# SoC.net
KiCad netlist of a schematic drawn in Altium Designer
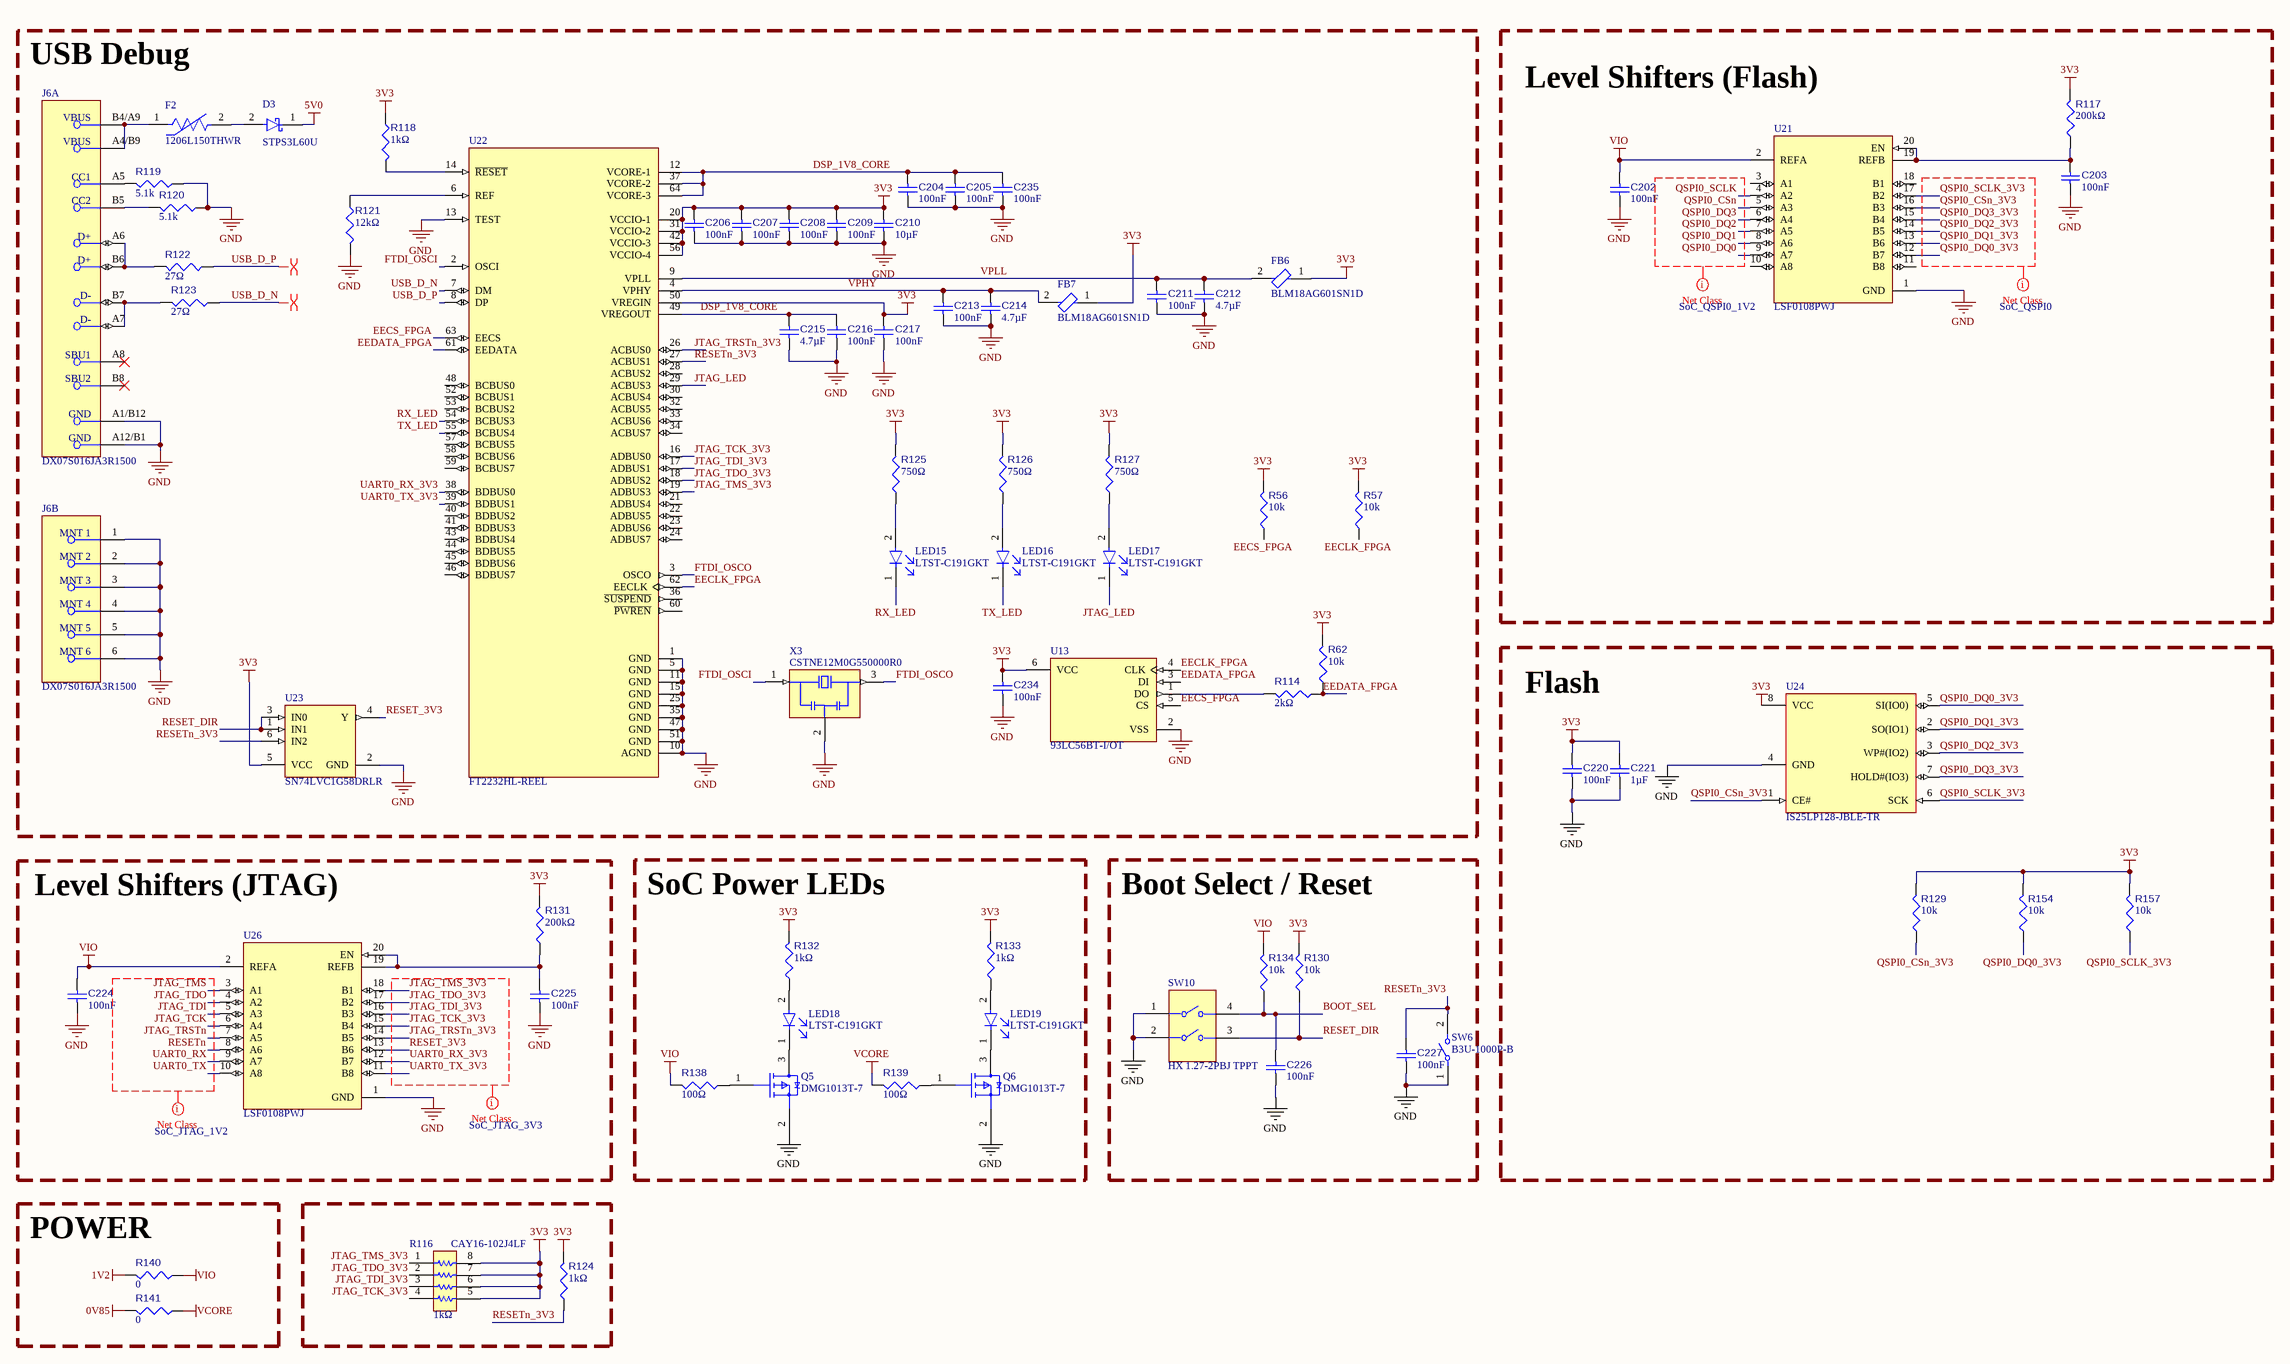
[diagram p0: SoC.SchDoc]

(export (version "E")
  (design (tool "Eeschema 10.0.6"))
  (components
    (comp (ref "C202")
      (value "100nF")
      (footprint "CAP-0402-MFG")
      (description "0402-100n-10%-16V-X7R-AECQ200")
      (fields (field (name "TOLERANCE") "10%") (field (name "MANUFACTURER PART NUMBER") "CL05B104KO5VPNC"))
      (libsource (lib "UC Berkeley – EE194") (part "CAP-NP-2P"))
    )
    (comp (ref "C203")
      (value "100nF")
      (footprint "CAP-0402-MFG")
      (description "0402-100n-10%-16V-X7R-AECQ200")
      (fields (field (name "TOLERANCE") "10%") (field (name "MANUFACTURER PART NUMBER") "CL05B104KO5VPNC"))
      (libsource (lib "UC Berkeley – EE194") (part "CAP-NP-2P"))
    )
    (comp (ref "C204")
      (value "100nF")
      (footprint "CAP-0402-MFG")
      (description "0402-100n-10%-16V-X7R-AECQ200")
      (fields (field (name "TOLERANCE") "10%") (field (name "MANUFACTURER PART NUMBER") "CL05B104KO5VPNC"))
      (libsource (lib "UC Berkeley – EE194") (part "CAP-NP-2P"))
    )
    (comp (ref "C205")
      (value "100nF")
      (footprint "CAP-0402-MFG")
      (description "0402-100n-10%-16V-X7R-AECQ200")
      (fields (field (name "TOLERANCE") "10%") (field (name "MANUFACTURER PART NUMBER") "CL05B104KO5VPNC"))
      (libsource (lib "UC Berkeley – EE194") (part "CAP-NP-2P"))
    )
    (comp (ref "C206")
      (value "100nF")
      (footprint "CAP-0402-MFG")
      (description "0402-100n-10%-16V-X7R-AECQ200")
      (fields (field (name "TOLERANCE") "10%") (field (name "MANUFACTURER PART NUMBER") "CL05B104KO5VPNC"))
      (libsource (lib "UC Berkeley – EE194") (part "CAP-NP-2P"))
    )
    (comp (ref "C207")
      (value "100nF")
      (footprint "CAP-0402-MFG")
      (description "0402-100n-10%-16V-X7R-AECQ200")
      (fields (field (name "TOLERANCE") "10%") (field (name "MANUFACTURER PART NUMBER") "CL05B104KO5VPNC"))
      (libsource (lib "UC Berkeley – EE194") (part "CAP-NP-2P"))
    )
    (comp (ref "C208")
      (value "100nF")
      (footprint "CAP-0402-MFG")
      (description "0402-100n-10%-16V-X7R-AECQ200")
      (fields (field (name "TOLERANCE") "10%") (field (name "MANUFACTURER PART NUMBER") "CL05B104KO5VPNC"))
      (libsource (lib "UC Berkeley – EE194") (part "CAP-NP-2P"))
    )
    (comp (ref "C209")
      (value "100nF")
      (footprint "CAP-0402-MFG")
      (description "0402-100n-10%-16V-X7R-AECQ200")
      (fields (field (name "TOLERANCE") "10%") (field (name "MANUFACTURER PART NUMBER") "CL05B104KO5VPNC"))
      (libsource (lib "UC Berkeley – EE194") (part "CAP-NP-2P"))
    )
    (comp (ref "C210")
      (value "10µF")
      (footprint "CAP-0603-MFG")
      (description "0603-10u-10%-16V-X5R-AECQ200")
      (fields (field (name "TOLERANCE") "10%") (field (name "MANUFACTURER PART NUMBER") "GRT188R61C106KE13J"))
      (libsource (lib "UC Berkeley – EE194") (part "CAP-NP-2P"))
    )
    (comp (ref "C211")
      (value "100nF")
      (footprint "CAP-0402-MFG")
      (description "0402-100n-10%-16V-X7R-AECQ200")
      (fields (field (name "TOLERANCE") "10%") (field (name "MANUFACTURER PART NUMBER") "CL05B104KO5VPNC"))
      (libsource (lib "UC Berkeley – EE194") (part "CAP-NP-2P"))
    )
    (comp (ref "C212")
      (value "4.7µF")
      (footprint "CAP-0402-MFG")
      (description "0402-4.7u-20%-25V-X5R")
      (fields (field (name "TOLERANCE") "20%") (field (name "MANUFACTURER PART NUMBER") "GRM155R61E475ME15D"))
      (libsource (lib "UC Berkeley – EE194") (part "CAP-NP-2P"))
    )
    (comp (ref "C213")
      (value "100nF")
      (footprint "CAP-0402-MFG")
      (description "0402-100n-10%-16V-X7R-AECQ200")
      (fields (field (name "TOLERANCE") "10%") (field (name "MANUFACTURER PART NUMBER") "CL05B104KO5VPNC"))
      (libsource (lib "UC Berkeley – EE194") (part "CAP-NP-2P"))
    )
    (comp (ref "C214")
      (value "4.7µF")
      (footprint "CAP-0402-MFG")
      (description "0402-4.7u-20%-25V-X5R")
      (fields (field (name "TOLERANCE") "20%") (field (name "MANUFACTURER PART NUMBER") "GRM155R61E475ME15D"))
      (libsource (lib "UC Berkeley – EE194") (part "CAP-NP-2P"))
    )
    (comp (ref "C215")
      (value "4.7µF")
      (footprint "CAP-0402-MFG")
      (description "0402-4.7u-20%-25V-X5R")
      (fields (field (name "TOLERANCE") "20%") (field (name "MANUFACTURER PART NUMBER") "GRM155R61E475ME15D"))
      (libsource (lib "UC Berkeley – EE194") (part "CAP-NP-2P"))
    )
    (comp (ref "C216")
      (value "100nF")
      (footprint "CAP-0402-MFG")
      (description "0402-100n-10%-16V-X7R-AECQ200")
      (fields (field (name "TOLERANCE") "10%") (field (name "MANUFACTURER PART NUMBER") "CL05B104KO5VPNC"))
      (libsource (lib "UC Berkeley – EE194") (part "CAP-NP-2P"))
    )
    (comp (ref "C217")
      (value "100nF")
      (footprint "CAP-0402-MFG")
      (description "0402-100n-10%-16V-X7R-AECQ200")
      (fields (field (name "TOLERANCE") "10%") (field (name "MANUFACTURER PART NUMBER") "CL05B104KO5VPNC"))
      (libsource (lib "UC Berkeley – EE194") (part "CAP-NP-2P"))
    )
    (comp (ref "C220")
      (value "100nF")
      (footprint "CAP-0402-MFG")
      (description "0402-100n-10%-16V-X7R-AECQ200")
      (fields (field (name "TOLERANCE") "10%") (field (name "MANUFACTURER PART NUMBER") "CL05B104KO5VPNC"))
      (libsource (lib "UC Berkeley – EE194") (part "CAP-NP-2P"))
    )
    (comp (ref "C221")
      (value "1µF")
      (footprint "CAP-0402-MFG")
      (description "0402-1u-10%-16V-X6S-AECQ200")
      (fields (field (name "MANUFACTURER PART NUMBER") "GRT155C81C105KE13J") (field (name "TOLERANCE") "10%"))
      (libsource (lib "UC Berkeley – EE194") (part "CAP-NP-2P"))
    )
    (comp (ref "C224")
      (value "100nF")
      (footprint "CAP-0402-MFG")
      (description "0402-100n-10%-16V-X7R-AECQ200")
      (fields (field (name "TOLERANCE") "10%") (field (name "MANUFACTURER PART NUMBER") "CL05B104KO5VPNC"))
      (libsource (lib "UC Berkeley – EE194") (part "CAP-NP-2P"))
    )
    (comp (ref "C225")
      (value "100nF")
      (footprint "CAP-0402-MFG")
      (description "0402-100n-10%-16V-X7R-AECQ200")
      (fields (field (name "TOLERANCE") "10%") (field (name "MANUFACTURER PART NUMBER") "CL05B104KO5VPNC"))
      (libsource (lib "UC Berkeley – EE194") (part "CAP-NP-2P"))
    )
    (comp (ref "C226")
      (value "100nF")
      (footprint "CAP-0402-MFG")
      (description "0402-100n-10%-16V-X7R-AECQ200")
      (fields (field (name "TOLERANCE") "10%") (field (name "MANUFACTURER PART NUMBER") "CL05B104KO5VPNC"))
      (libsource (lib "UC Berkeley – EE194") (part "CAP-NP-2P"))
    )
    (comp (ref "C227")
      (value "100nF")
      (footprint "CAP-0402-MFG")
      (description "0402-100n-10%-16V-X7R-AECQ200")
      (fields (field (name "TOLERANCE") "10%") (field (name "MANUFACTURER PART NUMBER") "CL05B104KO5VPNC"))
      (libsource (lib "UC Berkeley – EE194") (part "CAP-NP-2P"))
    )
    (comp (ref "C234")
      (value "100nF")
      (footprint "CAP-0402-MFG")
      (description "0402-100n-10%-16V-X7R-AECQ200")
      (fields (field (name "TOLERANCE") "10%") (field (name "MANUFACTURER PART NUMBER") "CL05B104KO5VPNC"))
      (libsource (lib "UC Berkeley – EE194") (part "CAP-NP-2P"))
    )
    (comp (ref "C235")
      (value "100nF")
      (footprint "CAP-0402-MFG")
      (description "0402-100n-10%-16V-X7R-AECQ200")
      (fields (field (name "TOLERANCE") "10%") (field (name "MANUFACTURER PART NUMBER") "CL05B104KO5VPNC"))
      (libsource (lib "UC Berkeley – EE194") (part "CAP-NP-2P"))
    )
    (comp (ref "D3")
      (value "STPS3L60U")
      (footprint "FP-DO214AA-MFG")
      (description "DO214AA-UNI-SCHOTTKY-60V-3A-590mV")
      (libsource (lib "UC Berkeley – EE194") (part "SCHOTTKY-UNI-2P-DIODE"))
    )
    (comp (ref "F2")
      (value "1206L150THWR")
      (footprint "FP-1206L050YR-MFG")
      (description "PTC Resettable Fuse 1.5A(hold) 3A(trip) 8VDC 100A 0.8W 0.3s 0.04Ohm SMD Solder Pad 1206 T/R")
      (libsource (lib "UC Berkeley – EE194") (part "FUSE-2P"))
    )
    (comp (ref "FB6")
      (value "BLM18AG601SN1D")
      (footprint "FERRITEBEAD-0603-MFG")
      (description "Ferrite Beads Multi-Layer 600Ohm 25% 100MHz 500mA 380mOhm DCR 0603 Automotive Paper T/R")
      (fields (field (name "TOLERANCE") "25%"))
      (libsource (lib "UC Berkeley – EE194") (part "FERRITE-BEAD-2P"))
    )
    (comp (ref "FB7")
      (value "BLM18AG601SN1D")
      (footprint "FERRITEBEAD-0603-MFG")
      (description "Ferrite Beads Multi-Layer 600Ohm 25% 100MHz 500mA 380mOhm DCR 0603 Automotive Paper T/R")
      (fields (field (name "TOLERANCE") "25%"))
      (libsource (lib "UC Berkeley – EE194") (part "FERRITE-BEAD-2P"))
    )
    (comp (ref "J6")
      (value "DX07S016JA3R1500")
      (footprint "FP-DX07S016JA3R1500-MFG")
      (description "Receptacle, 16 Position, 1-Row SMT, without Rear Shield, Shell-DIP Length 1.2mm")
      (libsource (lib "UC Berkeley – EE194") (part "DX07S016JA3R1500"))
    )
    (comp (ref "LED15")
      (value "LTST-C191GKT")
      (footprint "LED-0603-MFG")
      (description "LED yellow green 0603 wavelength 569nm light intensity 12mcd Front Mounting")
      (libsource (lib "UC Berkeley – EE194") (part "LED"))
    )
    (comp (ref "LED16")
      (value "LTST-C191GKT")
      (footprint "LED-0603-MFG")
      (description "LED yellow green 0603 wavelength 569nm light intensity 12mcd Front Mounting")
      (libsource (lib "UC Berkeley – EE194") (part "LED"))
    )
    (comp (ref "LED17")
      (value "LTST-C191GKT")
      (footprint "LED-0603-MFG")
      (description "LED yellow green 0603 wavelength 569nm light intensity 12mcd Front Mounting")
      (libsource (lib "UC Berkeley – EE194") (part "LED"))
    )
    (comp (ref "LED18")
      (value "LTST-C191GKT")
      (footprint "LED-0603-MFG")
      (description "LED yellow green 0603 wavelength 569nm light intensity 12mcd Front Mounting")
      (libsource (lib "UC Berkeley – EE194") (part "LED"))
    )
    (comp (ref "LED19")
      (value "LTST-C191GKT")
      (footprint "LED-0603-MFG")
      (description "LED yellow green 0603 wavelength 569nm light intensity 12mcd Front Mounting")
      (libsource (lib "UC Berkeley – EE194") (part "LED"))
    )
    (comp (ref "Q5")
      (value "DMG1013T-7")
      (footprint "FP-SOT523-MFG")
      (description "P-Channel 20 V 0.7 Ohm 0.27 W Enhancement Mode Mosfet - SOT-523")
      (libsource (lib "UC Berkeley – EE194") (part "P-MOSFET-3P"))
    )
    (comp (ref "Q6")
      (value "DMG1013T-7")
      (footprint "FP-SOT523-MFG")
      (description "P-Channel 20 V 0.7 Ohm 0.27 W Enhancement Mode Mosfet - SOT-523")
      (libsource (lib "UC Berkeley – EE194") (part "P-MOSFET-3P"))
    )
    (comp (ref "R56")
      (value "10k")
      (footprint "RES-0402")
      (description "0402-10k-1%-1/16W-AEC-Q200")
      (fields (field (name "TOLERANCE") "1%") (field (name "MANUFACTURER PART NUMBER") "AC0402FR-0710KL"))
      (libsource (lib "UC Berkeley – EE194") (part "RES-2P"))
    )
    (comp (ref "R57")
      (value "10k")
      (footprint "RES-0402")
      (description "0402-10k-1%-1/16W-AEC-Q200")
      (fields (field (name "TOLERANCE") "1%") (field (name "MANUFACTURER PART NUMBER") "AC0402FR-0710KL"))
      (libsource (lib "UC Berkeley – EE194") (part "RES-2P"))
    )
    (comp (ref "R62")
      (value "10k")
      (footprint "RES-0402")
      (description "0402-10k-1%-1/16W-AEC-Q200")
      (fields (field (name "TOLERANCE") "1%") (field (name "MANUFACTURER PART NUMBER") "AC0402FR-0710KL"))
      (libsource (lib "UC Berkeley – EE194") (part "RES-2P"))
    )
    (comp (ref "R114")
      (value "2kΩ")
      (footprint "RES-0402")
      (description "0402-2k-1%-1/16W-AEC-Q200")
      (fields (field (name "TOLERANCE") "1%") (field (name "POWER") "63mW"))
      (libsource (lib "UC Berkeley – EE194") (part "RES-2P"))
    )
    (comp (ref "R116")
      (value "CAY16-102J4LF")
      (footprint "RES-4x0603-MFG")
      (description "Res Thick Film Array 1K Ohm 5% 0.25W(1/4W) ±200ppm/C ISOL 8-Pin 1206(4 X 0603) Convex SMD T/R")
      (fields (field (name "TOLERANCE") "5%") (field (name "ALTIUM_VALUE") "1kΩ"))
      (libsource (lib "UC Berkeley – EE194") (part "RES-x4-8P"))
    )
    (comp (ref "R117")
      (value "200kΩ")
      (footprint "RES-0402")
      (description "0402-200k-1%-1/16W-AEC-Q200")
      (fields (field (name "TOLERANCE") "1%") (field (name "POWER") "63mW"))
      (libsource (lib "UC Berkeley – EE194") (part "RES-2P"))
    )
    (comp (ref "R118")
      (value "1kΩ")
      (footprint "RES-0402")
      (description "0402-1k-1%-1/16W-AEC-Q200")
      (fields (field (name "MANUFACTURER PART NUMBER") "AC0402FR-071KL") (field (name "POWER") "63mW"))
      (libsource (lib "UC Berkeley – EE194") (part "RES-2P"))
    )
    (comp (ref "R119")
      (value "5.1k")
      (footprint "RES-0402")
      (description "0402-5.1k-1%-1/16W-AEC-Q200")
      (fields (field (name "TOLERANCE") "1%") (field (name "MANUFACTURER PART NUMBER") "AC0402FR-075K1L"))
      (libsource (lib "UC Berkeley – EE194") (part "RES-2P"))
    )
    (comp (ref "R120")
      (value "5.1k")
      (footprint "RES-0402")
      (description "0402-5.1k-1%-1/16W-AEC-Q200")
      (fields (field (name "TOLERANCE") "1%") (field (name "MANUFACTURER PART NUMBER") "AC0402FR-075K1L"))
      (libsource (lib "UC Berkeley – EE194") (part "RES-2P"))
    )
    (comp (ref "R121")
      (value "12kΩ")
      (footprint "RES-0402")
      (description "0402-12k-1%-1/16W-AEC-Q200")
      (fields (field (name "POWER") "63mW") (field (name "TOLERANCE") "1%"))
      (libsource (lib "UC Berkeley – EE194") (part "RES-2P"))
    )
    (comp (ref "R122")
      (value "27Ω")
      (footprint "RES-0402")
      (description "0402-27-1%-1/16W-AEC-Q200")
      (fields (field (name "TOLERANCE") "1%") (field (name "MANUFACTURER PART NUMBER") "AC0402FR-0727RL"))
      (libsource (lib "UC Berkeley – EE194") (part "RES-2P"))
    )
    (comp (ref "R123")
      (value "27Ω")
      (footprint "RES-0402")
      (description "0402-27-1%-1/16W-AEC-Q200")
      (fields (field (name "TOLERANCE") "1%") (field (name "MANUFACTURER PART NUMBER") "AC0402FR-0727RL"))
      (libsource (lib "UC Berkeley – EE194") (part "RES-2P"))
    )
    (comp (ref "R124")
      (value "1kΩ")
      (footprint "RES-0402")
      (description "0402-1k-1%-1/16W-AEC-Q200")
      (fields (field (name "MANUFACTURER PART NUMBER") "AC0402FR-071KL") (field (name "POWER") "63mW"))
      (libsource (lib "UC Berkeley – EE194") (part "RES-2P"))
    )
    (comp (ref "R125")
      (value "750Ω")
      (footprint "RES-0402")
      (description "0402-750-1%-1/16W-AEC-Q200")
      (fields (field (name "TOLERANCE") "1%") (field (name "POWER") "63mW"))
      (libsource (lib "UC Berkeley – EE194") (part "RES-2P"))
    )
    (comp (ref "R126")
      (value "750Ω")
      (footprint "RES-0402")
      (description "0402-750-1%-1/16W-AEC-Q200")
      (fields (field (name "TOLERANCE") "1%") (field (name "POWER") "63mW"))
      (libsource (lib "UC Berkeley – EE194") (part "RES-2P"))
    )
    (comp (ref "R127")
      (value "750Ω")
      (footprint "RES-0402")
      (description "0402-750-1%-1/16W-AEC-Q200")
      (fields (field (name "TOLERANCE") "1%") (field (name "POWER") "63mW"))
      (libsource (lib "UC Berkeley – EE194") (part "RES-2P"))
    )
    (comp (ref "R129")
      (value "10k")
      (footprint "RES-0402")
      (description "0402-10k-1%-1/16W-AEC-Q200")
      (fields (field (name "TOLERANCE") "1%") (field (name "MANUFACTURER PART NUMBER") "AC0402FR-0710KL"))
      (libsource (lib "UC Berkeley – EE194") (part "RES-2P"))
    )
    (comp (ref "R130")
      (value "10k")
      (footprint "RES-0402")
      (description "0402-10k-1%-1/16W-AEC-Q200")
      (fields (field (name "TOLERANCE") "1%") (field (name "MANUFACTURER PART NUMBER") "AC0402FR-0710KL"))
      (libsource (lib "UC Berkeley – EE194") (part "RES-2P"))
    )
    (comp (ref "R131")
      (value "200kΩ")
      (footprint "RES-0402")
      (description "0402-200k-1%-1/16W-AEC-Q200")
      (fields (field (name "TOLERANCE") "1%") (field (name "POWER") "63mW"))
      (libsource (lib "UC Berkeley – EE194") (part "RES-2P"))
    )
    (comp (ref "R132")
      (value "1kΩ")
      (footprint "RES-0402")
      (description "0402-1k-1%-1/16W-AEC-Q200")
      (fields (field (name "MANUFACTURER PART NUMBER") "AC0402FR-071KL") (field (name "POWER") "63mW"))
      (libsource (lib "UC Berkeley – EE194") (part "RES-2P"))
    )
    (comp (ref "R133")
      (value "1kΩ")
      (footprint "RES-0402")
      (description "0402-1k-1%-1/16W-AEC-Q200")
      (fields (field (name "MANUFACTURER PART NUMBER") "AC0402FR-071KL") (field (name "POWER") "63mW"))
      (libsource (lib "UC Berkeley – EE194") (part "RES-2P"))
    )
    (comp (ref "R134")
      (value "10k")
      (footprint "RES-0402")
      (description "0402-10k-1%-1/16W-AEC-Q200")
      (fields (field (name "TOLERANCE") "1%") (field (name "MANUFACTURER PART NUMBER") "AC0402FR-0710KL"))
      (libsource (lib "UC Berkeley – EE194") (part "RES-2P"))
    )
    (comp (ref "R138")
      (value "100Ω")
      (footprint "RES-0402")
      (description "0402-100-1%-1/16W-AEC-Q200")
      (fields (field (name "MANUFACTURER PART NUMBER") "AC0402FR-07100RL") (field (name "POWER") "63mW"))
      (libsource (lib "UC Berkeley – EE194") (part "RES-2P"))
    )
    (comp (ref "R139")
      (value "100Ω")
      (footprint "RES-0402")
      (description "0402-100-1%-1/16W-AEC-Q200")
      (fields (field (name "MANUFACTURER PART NUMBER") "AC0402FR-07100RL") (field (name "POWER") "63mW"))
      (libsource (lib "UC Berkeley – EE194") (part "RES-2P"))
    )
    (comp (ref "R140")
      (value "0")
      (footprint "RES-0603-MFG")
      (description "0603-0-1A-AECQ200")
      (fields (field (name "MANUFACTURER PART NUMBER") "AC0603FR-070RL") (field (name "TOLERANCE") "1%"))
      (libsource (lib "UC Berkeley – EE194") (part "RES-2P"))
    )
    (comp (ref "R141")
      (value "0")
      (footprint "RES-0603-MFG")
      (description "0603-0-1A-AECQ200")
      (fields (field (name "MANUFACTURER PART NUMBER") "AC0603FR-070RL") (field (name "TOLERANCE") "1%"))
      (libsource (lib "UC Berkeley – EE194") (part "RES-2P"))
    )
    (comp (ref "R154")
      (value "10k")
      (footprint "RES-0402")
      (description "0402-10k-1%-1/16W-AEC-Q200")
      (fields (field (name "TOLERANCE") "1%") (field (name "MANUFACTURER PART NUMBER") "AC0402FR-0710KL"))
      (libsource (lib "UC Berkeley – EE194") (part "RES-2P"))
    )
    (comp (ref "R157")
      (value "10k")
      (footprint "RES-0402")
      (description "0402-10k-1%-1/16W-AEC-Q200")
      (fields (field (name "TOLERANCE") "1%") (field (name "MANUFACTURER PART NUMBER") "AC0402FR-0710KL"))
      (libsource (lib "UC Berkeley – EE194") (part "RES-2P"))
    )
    (comp (ref "SW6")
      (value "B3U-1000P-B")
      (footprint "FP-B3U-1000P-B-MFG")
      (description "Switch Tactile N.O. SPST Round Button Gull Wing 0.05A 12VDC 1.5N SMD Embossed T/R")
      (libsource (lib "UC Berkeley – EE194") (part "SWITCH-SPST-OFF-MOM-2P"))
    )
    (comp (ref "SW10")
      (value "HX 1.27-2PBJ TPPT")
      (footprint "HX 1.27-2PBJ TPPT-Footprint-1")
      (description "Dual 1.27mm SMT DIP Switch")
      (libsource (lib "UC Berkeley – EE194") (part "HX 1.27-2PBJ TPPT-Symbol-1"))
    )
    (comp (ref "U13")
      (value "93LC56BT-I/OT")
      (footprint "FP-SOT-23-6-MFG")
      (description "Microwire Serial EEPROM Family, 2.5Vto 5.5V' 2 MHz, -40°Cto 125°C, SOT-23-6, RoHS")
      (libsource (lib "UC Berkeley – EE194") (part "93LC56BT-I/OT"))
    )
    (comp (ref "U21")
      (value "LSF0108PWJ")
      (footprint "FP-TSSOP20-MFG")
      (description "LSF0108 - 8-bit bidirectional multi-voltage level translator; open-drain; push-pull")
      (libsource (lib "UC Berkeley – EE194") (part "LSF0108PWJ"))
    )
    (comp (ref "U22")
      (value "FT2232HL-REEL")
      (footprint "LQFP-64-MFG")
      (description "USB Hi-Speed to Dual Channel Serial UART/FIFO/JTAG/SPI/I2C IC - LQFP-64")
      (libsource (lib "UC Berkeley – EE194") (part "FT2232HL-REEL"))
    )
    (comp (ref "U23")
      (value "SN74LVC1G58DRLR")
      (footprint "DRL0006A_M")
      (description "Configurable Multiple-Function Gate 6-SOT-5X3 -40 to 125")
      (libsource (lib "UC Berkeley – EE194") (part "TI-SN74XXX1GXX-6"))
    )
    (comp (ref "U24")
      (value "IS25LP128-JBLE-TR")
      (footprint "FP-SOIC8-MFG")
      (description "NOR Flash Serial (SPI, Dual SPI, Quad SPI) 2.5V/3V/3.3V 128M-bit 16M x 8 8ns 8-Pin SOIC T/R")
      (fields (field (name "COPYRIGHT") "Copyright (C) 2025 Ultra Librarian. All rights reserved."))
      (libsource (lib "UC Berkeley – EE194") (part "IS25LP128-JBLE-TR"))
    )
    (comp (ref "U26")
      (value "LSF0108PWJ")
      (footprint "FP-TSSOP20-MFG")
      (description "LSF0108 - 8-bit bidirectional multi-voltage level translator; open-drain; push-pull")
      (libsource (lib "UC Berkeley – EE194") (part "LSF0108PWJ"))
    )
    (comp (ref "X3")
      (value "CSTNE12M0G550000R0")
      (footprint "OSC-SMD3213-3P")
      (description "Ceramic Resonator 12MHz ±0.5% (Tol) ±0.2% (Stability) 33pF 30Ohm 3-Pin CSMD T/R")
      (libsource (lib "UC Berkeley – EE194") (part "CSTNE12M0G550000R0"))
    )
  )
  (nets
    (net (code "2") (name "/BOOT_SEL") (class "Default")
      (node (ref "C226") (pin "1") (pinfunction "1_1") (pintype "passive"))
      (node (ref "R134") (pin "1") (pinfunction "1_1") (pintype "passive"))
      (node (ref "SW10") (pin "4") (pinfunction "4_4") (pintype "passive"))
    )
    (net (code "3") (name "/DSP_1V8_CORE") (class "Default")
      (node (ref "C204") (pin "1") (pinfunction "1_1") (pintype "passive"))
      (node (ref "C205") (pin "1") (pinfunction "1_1") (pintype "passive"))
      (node (ref "C215") (pin "1") (pinfunction "1_1") (pintype "passive"))
      (node (ref "C216") (pin "1") (pinfunction "1_1") (pintype "passive"))
      (node (ref "C235") (pin "1") (pinfunction "1_1") (pintype "passive"))
      (node (ref "U22") (pin "12") (pinfunction "VCORE-1_12") (pintype "power_in"))
      (node (ref "U22") (pin "37") (pinfunction "VCORE-2_37") (pintype "power_in"))
      (node (ref "U22") (pin "49") (pinfunction "VREGOUT_49") (pintype "power_in"))
      (node (ref "U22") (pin "64") (pinfunction "VCORE-3_64") (pintype "power_in"))
    )
    (net (code "4") (name "/EECLK_FPGA") (class "Default")
      (node (ref "R57") (pin "1") (pinfunction "1_1") (pintype "passive"))
      (node (ref "U13") (pin "4") (pinfunction "CLK_4") (pintype "input"))
      (node (ref "U22") (pin "62") (pinfunction "EECLK_62") (pintype "output"))
    )
    (net (code "5") (name "/EECS_FPGA") (class "Default")
      (node (ref "R56") (pin "1") (pinfunction "1_1") (pintype "passive"))
      (node (ref "U13") (pin "5") (pinfunction "CS_5") (pintype "input"))
      (node (ref "U22") (pin "63") (pinfunction "EECS_63") (pintype "bidirectional"))
    )
    (net (code "6") (name "/EEDATA_FPGA") (class "Default")
      (node (ref "R114") (pin "1") (pinfunction "1_1") (pintype "passive"))
      (node (ref "R62") (pin "1") (pinfunction "1_1") (pintype "passive"))
      (node (ref "U13") (pin "3") (pinfunction "DI_3") (pintype "input"))
      (node (ref "U22") (pin "61") (pinfunction "EEDATA_61") (pintype "bidirectional"))
    )
    (net (code "7") (name "/FTDI_OSCI") (class "Default")
      (node (ref "U22") (pin "2") (pinfunction "OSCI_2") (pintype "input"))
      (node (ref "X3") (pin "1") (pinfunction "IN_1") (pintype "input"))
    )
    (net (code "8") (name "/FTDI_OSCO") (class "Default")
      (node (ref "U22") (pin "3") (pinfunction "OSCO_3") (pintype "output"))
      (node (ref "X3") (pin "3") (pinfunction "OUT_3") (pintype "output"))
    )
    (net (code "9") (name "/JTAG_LED") (class "Default")
      (node (ref "LED17") (pin "1") (pinfunction "C_1") (pintype "passive"))
      (node (ref "U22") (pin "29") (pinfunction "ACBUS3_29") (pintype "bidirectional"))
    )
    (net (code "10") (name "/JTAG_TCK") (class "Default")
      (node (ref "U26") (pin "6") (pinfunction "A4_6") (pintype "bidirectional"))
    )
    (net (code "11") (name "/JTAG_TCK_3V3") (class "Default")
      (node (ref "R116") (pin "4") (pinfunction "4_4") (pintype "passive"))
      (node (ref "U22") (pin "16") (pinfunction "ADBUS0_16") (pintype "bidirectional"))
      (node (ref "U26") (pin "15") (pinfunction "B4_15") (pintype "bidirectional"))
    )
    (net (code "12") (name "/JTAG_TDI") (class "Default")
      (node (ref "U26") (pin "5") (pinfunction "A3_5") (pintype "bidirectional"))
    )
    (net (code "13") (name "/JTAG_TDI_3V3") (class "Default")
      (node (ref "R116") (pin "3") (pinfunction "3_3") (pintype "passive"))
      (node (ref "U22") (pin "17") (pinfunction "ADBUS1_17") (pintype "bidirectional"))
      (node (ref "U26") (pin "16") (pinfunction "B3_16") (pintype "bidirectional"))
    )
    (net (code "14") (name "/JTAG_TDO") (class "Default")
      (node (ref "U26") (pin "4") (pinfunction "A2_4") (pintype "bidirectional"))
    )
    (net (code "15") (name "/JTAG_TDO_3V3") (class "Default")
      (node (ref "R116") (pin "2") (pinfunction "2_2") (pintype "passive"))
      (node (ref "U22") (pin "18") (pinfunction "ADBUS2_18") (pintype "bidirectional"))
      (node (ref "U26") (pin "17") (pinfunction "B2_17") (pintype "bidirectional"))
    )
    (net (code "16") (name "/JTAG_TMS") (class "Default")
      (node (ref "U26") (pin "3") (pinfunction "A1_3") (pintype "bidirectional"))
    )
    (net (code "17") (name "/JTAG_TMS_3V3") (class "Default")
      (node (ref "R116") (pin "1") (pinfunction "1_1") (pintype "passive"))
      (node (ref "U22") (pin "19") (pinfunction "ADBUS3_19") (pintype "bidirectional"))
      (node (ref "U26") (pin "18") (pinfunction "B1_18") (pintype "bidirectional"))
    )
    (net (code "18") (name "/JTAG_TRSTn") (class "Default")
      (node (ref "U26") (pin "7") (pinfunction "A5_7") (pintype "bidirectional"))
    )
    (net (code "19") (name "/JTAG_TRSTn_3V3") (class "Default")
      (node (ref "U22") (pin "26") (pinfunction "ACBUS0_26") (pintype "bidirectional"))
      (node (ref "U26") (pin "14") (pinfunction "B5_14") (pintype "bidirectional"))
    )
    (net (code "20") (name "/QSPI0_CSn") (class "Default")
      (node (ref "U21") (pin "5") (pinfunction "A3_5") (pintype "bidirectional"))
    )
    (net (code "21") (name "/QSPI0_CSn_3V3") (class "Default")
      (node (ref "R129") (pin "1") (pinfunction "1_1") (pintype "passive"))
      (node (ref "U21") (pin "16") (pinfunction "B3_16") (pintype "bidirectional"))
      (node (ref "U24") (pin "1") (pinfunction "CE#_1") (pintype "input"))
    )
    (net (code "22") (name "/QSPI0_DQ0") (class "Default")
      (node (ref "U21") (pin "9") (pinfunction "A7_9") (pintype "bidirectional"))
    )
    (net (code "23") (name "/QSPI0_DQ0_3V3") (class "Default")
      (node (ref "R154") (pin "1") (pinfunction "1_1") (pintype "passive"))
      (node (ref "U21") (pin "12") (pinfunction "B7_12") (pintype "bidirectional"))
      (node (ref "U24") (pin "5") (pinfunction "SI(IO0)_5") (pintype "bidirectional"))
    )
    (net (code "24") (name "/QSPI0_DQ1") (class "Default")
      (node (ref "U21") (pin "8") (pinfunction "A6_8") (pintype "bidirectional"))
    )
    (net (code "25") (name "/QSPI0_DQ1_3V3") (class "Default")
      (node (ref "U21") (pin "13") (pinfunction "B6_13") (pintype "bidirectional"))
      (node (ref "U24") (pin "2") (pinfunction "SO(IO1)_2") (pintype "bidirectional"))
    )
    (net (code "26") (name "/QSPI0_DQ2") (class "Default")
      (node (ref "U21") (pin "7") (pinfunction "A5_7") (pintype "bidirectional"))
    )
    (net (code "27") (name "/QSPI0_DQ2_3V3") (class "Default")
      (node (ref "U21") (pin "14") (pinfunction "B5_14") (pintype "bidirectional"))
      (node (ref "U24") (pin "3") (pinfunction "WP#(IO2)_3") (pintype "bidirectional"))
    )
    (net (code "28") (name "/QSPI0_DQ3") (class "Default")
      (node (ref "U21") (pin "6") (pinfunction "A4_6") (pintype "bidirectional"))
    )
    (net (code "29") (name "/QSPI0_DQ3_3V3") (class "Default")
      (node (ref "U21") (pin "15") (pinfunction "B4_15") (pintype "bidirectional"))
      (node (ref "U24") (pin "7") (pinfunction "HOLD#(IO3)_7") (pintype "bidirectional"))
    )
    (net (code "30") (name "/QSPI0_SCLK") (class "Default")
      (node (ref "U21") (pin "4") (pinfunction "A2_4") (pintype "bidirectional"))
    )
    (net (code "31") (name "/QSPI0_SCLK_3V3") (class "Default")
      (node (ref "R157") (pin "1") (pinfunction "1_1") (pintype "passive"))
      (node (ref "U21") (pin "17") (pinfunction "B2_17") (pintype "bidirectional"))
      (node (ref "U24") (pin "6") (pinfunction "SCK_6") (pintype "input"))
    )
    (net (code "32") (name "/RESET_3V3") (class "Default")
      (node (ref "U23") (pin "4") (pinfunction "Y_4") (pintype "output"))
      (node (ref "U26") (pin "13") (pinfunction "B6_13") (pintype "bidirectional"))
    )
    (net (code "33") (name "/RESET_DIR") (class "Default")
      (node (ref "R130") (pin "1") (pinfunction "1_1") (pintype "passive"))
      (node (ref "SW10") (pin "3") (pinfunction "3_3") (pintype "passive"))
      (node (ref "U23") (pin "1") (pinfunction "IN1_1") (pintype "input"))
      (node (ref "U23") (pin "3") (pinfunction "IN0_3") (pintype "input"))
    )
    (net (code "34") (name "/RESETn") (class "Default")
      (node (ref "U26") (pin "8") (pinfunction "A6_8") (pintype "bidirectional"))
    )
    (net (code "35") (name "/RESETn_3V3") (class "Default")
      (node (ref "C227") (pin "1") (pinfunction "1_1") (pintype "passive"))
      (node (ref "R124") (pin "1") (pinfunction "1_1") (pintype "passive"))
      (node (ref "SW6") (pin "2") (pinfunction "2_2") (pintype "passive"))
      (node (ref "U22") (pin "27") (pinfunction "ACBUS1_27") (pintype "bidirectional"))
      (node (ref "U23") (pin "6") (pinfunction "IN2_6") (pintype "input"))
    )
    (net (code "36") (name "/RX_LED") (class "Default")
      (node (ref "LED15") (pin "1") (pinfunction "C_1") (pintype "passive"))
      (node (ref "U22") (pin "54") (pinfunction "BCBUS3_54") (pintype "bidirectional"))
    )
    (net (code "37") (name "/TX_LED") (class "Default")
      (node (ref "LED16") (pin "1") (pinfunction "C_1") (pintype "passive"))
      (node (ref "U22") (pin "55") (pinfunction "BCBUS4_55") (pintype "bidirectional"))
    )
    (net (code "38") (name "/UART0_RX") (class "Default")
      (node (ref "U26") (pin "9") (pinfunction "A7_9") (pintype "bidirectional"))
    )
    (net (code "39") (name "/UART0_RX_3V3") (class "Default")
      (node (ref "U22") (pin "38") (pinfunction "BDBUS0_38") (pintype "bidirectional"))
      (node (ref "U26") (pin "12") (pinfunction "B7_12") (pintype "bidirectional"))
    )
    (net (code "40") (name "/UART0_TX") (class "Default")
      (node (ref "U26") (pin "10") (pinfunction "A8_10") (pintype "bidirectional"))
    )
    (net (code "41") (name "/UART0_TX_3V3") (class "Default")
      (node (ref "U22") (pin "39") (pinfunction "BDBUS1_39") (pintype "bidirectional"))
      (node (ref "U26") (pin "11") (pinfunction "B8_11") (pintype "bidirectional"))
    )
    (net (code "42") (name "/USB_D_N") (class "Default")
      (node (ref "R123") (pin "1") (pinfunction "1_1") (pintype "passive"))
      (node (ref "U22") (pin "7") (pinfunction "DM_7") (pintype "bidirectional"))
    )
    (net (code "43") (name "/USB_D_P") (class "Default")
      (node (ref "R122") (pin "1") (pinfunction "1_1") (pintype "passive"))
      (node (ref "U22") (pin "8") (pinfunction "DP_8") (pintype "bidirectional"))
    )
    (net (code "44") (name "/VPHY") (class "Default")
      (node (ref "C213") (pin "1") (pinfunction "1_1") (pintype "passive"))
      (node (ref "C214") (pin "1") (pinfunction "1_1") (pintype "passive"))
      (node (ref "FB7") (pin "2") (pinfunction "2_2") (pintype "passive"))
      (node (ref "U22") (pin "4") (pinfunction "VPHY_4") (pintype "power_in"))
    )
    (net (code "45") (name "/VPLL") (class "Default")
      (node (ref "C211") (pin "1") (pinfunction "1_1") (pintype "passive"))
      (node (ref "C212") (pin "1") (pinfunction "1_1") (pintype "passive"))
      (node (ref "FB6") (pin "2") (pinfunction "2_2") (pintype "passive"))
      (node (ref "U22") (pin "9") (pinfunction "VPLL_9") (pintype "power_in"))
    )
    (net (code "46") (name "0V85") (class "Default")
      (node (ref "R141") (pin "2") (pinfunction "2_2") (pintype "passive"))
    )
    (net (code "47") (name "1V2") (class "Default")
      (node (ref "R140") (pin "2") (pinfunction "2_2") (pintype "passive"))
    )
    (net (code "48") (name "3V3") (class "Default")
      (node (ref "C206") (pin "1") (pinfunction "1_1") (pintype "passive"))
      (node (ref "C207") (pin "2") (pinfunction "2_2") (pintype "passive"))
      (node (ref "C208") (pin "1") (pinfunction "1_1") (pintype "passive"))
      (node (ref "C209") (pin "1") (pinfunction "1_1") (pintype "passive"))
      (node (ref "C210") (pin "1") (pinfunction "1_1") (pintype "passive"))
      (node (ref "C217") (pin "1") (pinfunction "1_1") (pintype "passive"))
      (node (ref "C220") (pin "1") (pinfunction "1_1") (pintype "passive"))
      (node (ref "C221") (pin "1") (pinfunction "1_1") (pintype "passive"))
      (node (ref "C234") (pin "2") (pinfunction "2_2") (pintype "passive"))
      (node (ref "FB6") (pin "1") (pinfunction "1_1") (pintype "passive"))
      (node (ref "FB7") (pin "1") (pinfunction "1_1") (pintype "passive"))
      (node (ref "R116") (pin "5") (pinfunction "5_5") (pintype "passive"))
      (node (ref "R116") (pin "6") (pinfunction "6_6") (pintype "passive"))
      (node (ref "R116") (pin "7") (pinfunction "7_7") (pintype "passive"))
      (node (ref "R116") (pin "8") (pinfunction "8_8") (pintype "passive"))
      (node (ref "R117") (pin "2") (pinfunction "2_2") (pintype "passive"))
      (node (ref "R118") (pin "1") (pinfunction "1_1") (pintype "passive"))
      (node (ref "R124") (pin "2") (pinfunction "2_2") (pintype "passive"))
      (node (ref "R125") (pin "2") (pinfunction "2_2") (pintype "passive"))
      (node (ref "R126") (pin "2") (pinfunction "2_2") (pintype "passive"))
      (node (ref "R127") (pin "2") (pinfunction "2_2") (pintype "passive"))
      (node (ref "R129") (pin "2") (pinfunction "2_2") (pintype "passive"))
      (node (ref "R130") (pin "2") (pinfunction "2_2") (pintype "passive"))
      (node (ref "R131") (pin "2") (pinfunction "2_2") (pintype "passive"))
      (node (ref "R132") (pin "2") (pinfunction "2_2") (pintype "passive"))
      (node (ref "R133") (pin "2") (pinfunction "2_2") (pintype "passive"))
      (node (ref "R154") (pin "2") (pinfunction "2_2") (pintype "passive"))
      (node (ref "R157") (pin "2") (pinfunction "2_2") (pintype "passive"))
      (node (ref "R56") (pin "2") (pinfunction "2_2") (pintype "passive"))
      (node (ref "R57") (pin "2") (pinfunction "2_2") (pintype "passive"))
      (node (ref "R62") (pin "2") (pinfunction "2_2") (pintype "passive"))
      (node (ref "U13") (pin "6") (pinfunction "VCC_6") (pintype "power_in"))
      (node (ref "U22") (pin "20") (pinfunction "VCCIO-1_20") (pintype "power_in"))
      (node (ref "U22") (pin "31") (pinfunction "VCCIO-2_31") (pintype "power_in"))
      (node (ref "U22") (pin "42") (pinfunction "VCCIO-3_42") (pintype "power_in"))
      (node (ref "U22") (pin "50") (pinfunction "VREGIN_50") (pintype "power_in"))
      (node (ref "U22") (pin "56") (pinfunction "VCCIO-4_56") (pintype "power_in"))
      (node (ref "U23") (pin "5") (pinfunction "VCC_5") (pintype "power_in"))
      (node (ref "U24") (pin "8") (pinfunction "VCC_8") (pintype "power_in"))
    )
    (net (code "49") (name "5V0") (class "Default")
      (node (ref "D3") (pin "1") (pinfunction "K_1") (pintype "passive"))
    )
    (net (code "50") (name "GND") (class "Default")
      (node (ref "C202") (pin "2") (pinfunction "2_2") (pintype "passive"))
      (node (ref "C203") (pin "2") (pinfunction "2_2") (pintype "passive"))
      (node (ref "C204") (pin "2") (pinfunction "2_2") (pintype "passive"))
      (node (ref "C205") (pin "2") (pinfunction "2_2") (pintype "passive"))
      (node (ref "C206") (pin "2") (pinfunction "2_2") (pintype "passive"))
      (node (ref "C207") (pin "1") (pinfunction "1_1") (pintype "passive"))
      (node (ref "C208") (pin "2") (pinfunction "2_2") (pintype "passive"))
      (node (ref "C209") (pin "2") (pinfunction "2_2") (pintype "passive"))
      (node (ref "C210") (pin "2") (pinfunction "2_2") (pintype "passive"))
      (node (ref "C211") (pin "2") (pinfunction "2_2") (pintype "passive"))
      (node (ref "C212") (pin "2") (pinfunction "2_2") (pintype "passive"))
      (node (ref "C213") (pin "2") (pinfunction "2_2") (pintype "passive"))
      (node (ref "C214") (pin "2") (pinfunction "2_2") (pintype "passive"))
      (node (ref "C215") (pin "2") (pinfunction "2_2") (pintype "passive"))
      (node (ref "C216") (pin "2") (pinfunction "2_2") (pintype "passive"))
      (node (ref "C217") (pin "2") (pinfunction "2_2") (pintype "passive"))
      (node (ref "C220") (pin "2") (pinfunction "2_2") (pintype "passive"))
      (node (ref "C221") (pin "2") (pinfunction "2_2") (pintype "passive"))
      (node (ref "C224") (pin "2") (pinfunction "2_2") (pintype "passive"))
      (node (ref "C225") (pin "2") (pinfunction "2_2") (pintype "passive"))
      (node (ref "C226") (pin "2") (pinfunction "2_2") (pintype "passive"))
      (node (ref "C227") (pin "2") (pinfunction "2_2") (pintype "passive"))
      (node (ref "C234") (pin "1") (pinfunction "1_1") (pintype "passive"))
      (node (ref "C235") (pin "2") (pinfunction "2_2") (pintype "passive"))
      (node (ref "J6") (pin "1") (pinfunction "MNT_1_1") (pintype "passive"))
      (node (ref "J6") (pin "2") (pinfunction "MNT_2_2") (pintype "passive"))
      (node (ref "J6") (pin "3") (pinfunction "MNT_3_3") (pintype "passive"))
      (node (ref "J6") (pin "4") (pinfunction "MNT_4_4") (pintype "passive"))
      (node (ref "J6") (pin "5") (pinfunction "MNT_5_5") (pintype "passive"))
      (node (ref "J6") (pin "6") (pinfunction "MNT_6_6") (pintype "passive"))
      (node (ref "J6") (pin "A1/B12") (pinfunction "GND_A1/B12") (pintype "power_in"))
      (node (ref "J6") (pin "A12/B1") (pinfunction "GND_A12/B1") (pintype "power_in"))
      (node (ref "Q5") (pin "2") (pinfunction "S_2") (pintype "passive"))
      (node (ref "Q6") (pin "2") (pinfunction "S_2") (pintype "passive"))
      (node (ref "R119") (pin "1") (pinfunction "1_1") (pintype "passive"))
      (node (ref "R120") (pin "1") (pinfunction "1_1") (pintype "passive"))
      (node (ref "R121") (pin "2") (pinfunction "2_2") (pintype "passive"))
      (node (ref "SW10") (pin "1") (pinfunction "1_1") (pintype "passive"))
      (node (ref "SW10") (pin "2") (pinfunction "2_2") (pintype "passive"))
      (node (ref "SW6") (pin "1") (pinfunction "1_1") (pintype "passive"))
      (node (ref "U13") (pin "2") (pinfunction "VSS_2") (pintype "power_in"))
      (node (ref "U21") (pin "1") (pinfunction "GND_1") (pintype "power_in"))
      (node (ref "U22") (pin "1") (pinfunction "GND_1") (pintype "power_in"))
      (node (ref "U22") (pin "10") (pinfunction "AGND_10") (pintype "power_in"))
      (node (ref "U22") (pin "11") (pinfunction "GND_11") (pintype "power_in"))
      (node (ref "U22") (pin "13") (pinfunction "TEST_13") (pintype "input"))
      (node (ref "U22") (pin "15") (pinfunction "GND_15") (pintype "power_in"))
      (node (ref "U22") (pin "25") (pinfunction "GND_25") (pintype "power_in"))
      (node (ref "U22") (pin "35") (pinfunction "GND_35") (pintype "power_in"))
      (node (ref "U22") (pin "47") (pinfunction "GND_47") (pintype "power_in"))
      (node (ref "U22") (pin "5") (pinfunction "GND_5") (pintype "power_in"))
      (node (ref "U22") (pin "51") (pinfunction "GND_51") (pintype "power_in"))
      (node (ref "U23") (pin "2") (pinfunction "GND_2") (pintype "power_in"))
      (node (ref "U24") (pin "4") (pinfunction "GND_4") (pintype "power_in"))
      (node (ref "U26") (pin "1") (pinfunction "GND_1") (pintype "power_in"))
      (node (ref "X3") (pin "2") (pinfunction "GND_2") (pintype "power_in"))
    )
    (net (code "51") (name "Net-(D3-A)") (class "Default")
      (node (ref "D3") (pin "2") (pinfunction "A_2") (pintype "passive"))
      (node (ref "F2") (pin "2") (pinfunction "2_2") (pintype "passive"))
    )
    (net (code "52") (name "Net-(F2-Pad1)") (class "Default")
      (node (ref "F2") (pin "1") (pinfunction "1_1") (pintype "passive"))
      (node (ref "J6") (pin "A4/B9") (pinfunction "VBUS_A4/B9") (pintype "power_in"))
      (node (ref "J6") (pin "B4/A9") (pinfunction "VBUS_B4/A9") (pintype "power_in"))
    )
    (net (code "53") (name "Net-(J6A-CC1)") (class "Default")
      (node (ref "J6") (pin "A5") (pinfunction "CC1_A5") (pintype "passive"))
      (node (ref "R119") (pin "2") (pinfunction "2_2") (pintype "passive"))
    )
    (net (code "54") (name "Net-(J6A-CC2)") (class "Default")
      (node (ref "J6") (pin "B5") (pinfunction "CC2_B5") (pintype "passive"))
      (node (ref "R120") (pin "2") (pinfunction "2_2") (pintype "passive"))
    )
    (net (code "55") (name "Net-(J6A-D+-PadA6)") (class "Default")
      (node (ref "J6") (pin "A6") (pinfunction "D+_A6") (pintype "bidirectional"))
      (node (ref "J6") (pin "B6") (pinfunction "D+_B6") (pintype "bidirectional"))
      (node (ref "R122") (pin "2") (pinfunction "2_2") (pintype "passive"))
    )
    (net (code "56") (name "Net-(J6A-D--PadA7)") (class "Default")
      (node (ref "J6") (pin "A7") (pinfunction "D-_A7") (pintype "bidirectional"))
      (node (ref "J6") (pin "B7") (pinfunction "D-_B7") (pintype "bidirectional"))
      (node (ref "R123") (pin "2") (pinfunction "2_2") (pintype "passive"))
    )
    (net (code "57") (name "Net-(LED15-A)") (class "Default")
      (node (ref "LED15") (pin "2") (pinfunction "A_2") (pintype "passive"))
      (node (ref "R125") (pin "1") (pinfunction "1_1") (pintype "passive"))
    )
    (net (code "58") (name "Net-(LED16-A)") (class "Default")
      (node (ref "LED16") (pin "2") (pinfunction "A_2") (pintype "passive"))
      (node (ref "R126") (pin "1") (pinfunction "1_1") (pintype "passive"))
    )
    (net (code "59") (name "Net-(LED17-A)") (class "Default")
      (node (ref "LED17") (pin "2") (pinfunction "A_2") (pintype "passive"))
      (node (ref "R127") (pin "1") (pinfunction "1_1") (pintype "passive"))
    )
    (net (code "60") (name "Net-(LED18-A)") (class "Default")
      (node (ref "LED18") (pin "2") (pinfunction "A_2") (pintype "passive"))
      (node (ref "R132") (pin "1") (pinfunction "1_1") (pintype "passive"))
    )
    (net (code "61") (name "Net-(LED18-C)") (class "Default")
      (node (ref "LED18") (pin "1") (pinfunction "C_1") (pintype "passive"))
      (node (ref "Q5") (pin "3") (pinfunction "D_3") (pintype "passive"))
    )
    (net (code "62") (name "Net-(LED19-A)") (class "Default")
      (node (ref "LED19") (pin "2") (pinfunction "A_2") (pintype "passive"))
      (node (ref "R133") (pin "1") (pinfunction "1_1") (pintype "passive"))
    )
    (net (code "63") (name "Net-(LED19-C)") (class "Default")
      (node (ref "LED19") (pin "1") (pinfunction "C_1") (pintype "passive"))
      (node (ref "Q6") (pin "3") (pinfunction "D_3") (pintype "passive"))
    )
    (net (code "64") (name "Net-(Q5-G)") (class "Default")
      (node (ref "Q5") (pin "1") (pinfunction "G_1") (pintype "passive"))
      (node (ref "R138") (pin "1") (pinfunction "1_1") (pintype "passive"))
    )
    (net (code "65") (name "Net-(Q6-G)") (class "Default")
      (node (ref "Q6") (pin "1") (pinfunction "G_1") (pintype "passive"))
      (node (ref "R139") (pin "1") (pinfunction "1_1") (pintype "passive"))
    )
    (net (code "66") (name "Net-(U13-DO)") (class "Default")
      (node (ref "R114") (pin "2") (pinfunction "2_2") (pintype "passive"))
      (node (ref "U13") (pin "1") (pinfunction "DO_1") (pintype "output"))
    )
    (net (code "67") (name "Net-(U21-EN)") (class "Default")
      (node (ref "C203") (pin "1") (pinfunction "1_1") (pintype "passive"))
      (node (ref "R117") (pin "1") (pinfunction "1_1") (pintype "passive"))
      (node (ref "U21") (pin "19") (pinfunction "REFB_19") (pintype "power_in"))
      (node (ref "U21") (pin "20") (pinfunction "EN_20") (pintype "input"))
    )
    (net (code "68") (name "Net-(U22-REF)") (class "Default")
      (node (ref "R121") (pin "1") (pinfunction "1_1") (pintype "passive"))
      (node (ref "U22") (pin "6") (pinfunction "REF_6") (pintype "input"))
    )
    (net (code "69") (name "Net-(U22-~{RESET})") (class "Default")
      (node (ref "R118") (pin "2") (pinfunction "2_2") (pintype "passive"))
      (node (ref "U22") (pin "14") (pinfunction "~{RESET}_14") (pintype "input"))
    )
    (net (code "70") (name "Net-(U26-EN)") (class "Default")
      (node (ref "C225") (pin "1") (pinfunction "1_1") (pintype "passive"))
      (node (ref "R131") (pin "1") (pinfunction "1_1") (pintype "passive"))
      (node (ref "U26") (pin "19") (pinfunction "REFB_19") (pintype "power_in"))
      (node (ref "U26") (pin "20") (pinfunction "EN_20") (pintype "input"))
    )
    (net (code "71") (name "VCORE") (class "Default")
      (node (ref "R139") (pin "2") (pinfunction "2_2") (pintype "passive"))
      (node (ref "R141") (pin "1") (pinfunction "1_1") (pintype "passive"))
    )
    (net (code "72") (name "VIO") (class "Default")
      (node (ref "C202") (pin "1") (pinfunction "1_1") (pintype "passive"))
      (node (ref "C224") (pin "1") (pinfunction "1_1") (pintype "passive"))
      (node (ref "R134") (pin "2") (pinfunction "2_2") (pintype "passive"))
      (node (ref "R138") (pin "2") (pinfunction "2_2") (pintype "passive"))
      (node (ref "R140") (pin "1") (pinfunction "1_1") (pintype "passive"))
      (node (ref "U21") (pin "2") (pinfunction "REFA_2") (pintype "power_in"))
      (node (ref "U26") (pin "2") (pinfunction "REFA_2") (pintype "power_in"))
    )
    (net (code "73") (name "unconnected-(J6A-SBU1-PadA8)") (class "Default")
      (node (ref "J6") (pin "A8") (pinfunction "SBU1_A8") (pintype "passive+no_connect"))
    )
    (net (code "74") (name "unconnected-(J6A-SBU2-PadB8)") (class "Default")
      (node (ref "J6") (pin "B8") (pinfunction "SBU2_B8") (pintype "passive+no_connect"))
    )
    (net (code "75") (name "unconnected-(U21-A1-Pad3)") (class "Default")
      (node (ref "U21") (pin "3") (pinfunction "A1_3") (pintype "bidirectional"))
    )
    (net (code "76") (name "unconnected-(U21-A8-Pad10)") (class "Default")
      (node (ref "U21") (pin "10") (pinfunction "A8_10") (pintype "bidirectional"))
    )
    (net (code "77") (name "unconnected-(U21-B1-Pad18)") (class "Default")
      (node (ref "U21") (pin "18") (pinfunction "B1_18") (pintype "bidirectional"))
    )
    (net (code "78") (name "unconnected-(U21-B8-Pad11)") (class "Default")
      (node (ref "U21") (pin "11") (pinfunction "B8_11") (pintype "bidirectional"))
    )
    (net (code "79") (name "unconnected-(U22-ACBUS2-Pad28)") (class "Default")
      (node (ref "U22") (pin "28") (pinfunction "ACBUS2_28") (pintype "bidirectional"))
    )
    (net (code "80") (name "unconnected-(U22-ACBUS4-Pad30)") (class "Default")
      (node (ref "U22") (pin "30") (pinfunction "ACBUS4_30") (pintype "bidirectional"))
    )
    (net (code "81") (name "unconnected-(U22-ACBUS5-Pad32)") (class "Default")
      (node (ref "U22") (pin "32") (pinfunction "ACBUS5_32") (pintype "bidirectional"))
    )
    (net (code "82") (name "unconnected-(U22-ACBUS6-Pad33)") (class "Default")
      (node (ref "U22") (pin "33") (pinfunction "ACBUS6_33") (pintype "bidirectional"))
    )
    (net (code "83") (name "unconnected-(U22-ACBUS7-Pad34)") (class "Default")
      (node (ref "U22") (pin "34") (pinfunction "ACBUS7_34") (pintype "bidirectional"))
    )
    (net (code "84") (name "unconnected-(U22-ADBUS4-Pad21)") (class "Default")
      (node (ref "U22") (pin "21") (pinfunction "ADBUS4_21") (pintype "bidirectional"))
    )
    (net (code "85") (name "unconnected-(U22-ADBUS5-Pad22)") (class "Default")
      (node (ref "U22") (pin "22") (pinfunction "ADBUS5_22") (pintype "bidirectional"))
    )
    (net (code "86") (name "unconnected-(U22-ADBUS6-Pad23)") (class "Default")
      (node (ref "U22") (pin "23") (pinfunction "ADBUS6_23") (pintype "bidirectional"))
    )
    (net (code "87") (name "unconnected-(U22-ADBUS7-Pad24)") (class "Default")
      (node (ref "U22") (pin "24") (pinfunction "ADBUS7_24") (pintype "bidirectional"))
    )
    (net (code "88") (name "unconnected-(U22-BCBUS0-Pad48)") (class "Default")
      (node (ref "U22") (pin "48") (pinfunction "BCBUS0_48") (pintype "bidirectional"))
    )
    (net (code "89") (name "unconnected-(U22-BCBUS1-Pad52)") (class "Default")
      (node (ref "U22") (pin "52") (pinfunction "BCBUS1_52") (pintype "bidirectional"))
    )
    (net (code "90") (name "unconnected-(U22-BCBUS2-Pad53)") (class "Default")
      (node (ref "U22") (pin "53") (pinfunction "BCBUS2_53") (pintype "bidirectional"))
    )
    (net (code "91") (name "unconnected-(U22-BCBUS5-Pad57)") (class "Default")
      (node (ref "U22") (pin "57") (pinfunction "BCBUS5_57") (pintype "bidirectional"))
    )
    (net (code "92") (name "unconnected-(U22-BCBUS6-Pad58)") (class "Default")
      (node (ref "U22") (pin "58") (pinfunction "BCBUS6_58") (pintype "bidirectional"))
    )
    (net (code "93") (name "unconnected-(U22-BCBUS7-Pad59)") (class "Default")
      (node (ref "U22") (pin "59") (pinfunction "BCBUS7_59") (pintype "bidirectional"))
    )
    (net (code "94") (name "unconnected-(U22-BDBUS2-Pad40)") (class "Default")
      (node (ref "U22") (pin "40") (pinfunction "BDBUS2_40") (pintype "bidirectional"))
    )
    (net (code "95") (name "unconnected-(U22-BDBUS3-Pad41)") (class "Default")
      (node (ref "U22") (pin "41") (pinfunction "BDBUS3_41") (pintype "bidirectional"))
    )
    (net (code "96") (name "unconnected-(U22-BDBUS4-Pad43)") (class "Default")
      (node (ref "U22") (pin "43") (pinfunction "BDBUS4_43") (pintype "bidirectional"))
    )
    (net (code "97") (name "unconnected-(U22-BDBUS5-Pad44)") (class "Default")
      (node (ref "U22") (pin "44") (pinfunction "BDBUS5_44") (pintype "bidirectional"))
    )
    (net (code "98") (name "unconnected-(U22-BDBUS6-Pad45)") (class "Default")
      (node (ref "U22") (pin "45") (pinfunction "BDBUS6_45") (pintype "bidirectional"))
    )
    (net (code "99") (name "unconnected-(U22-BDBUS7-Pad46)") (class "Default")
      (node (ref "U22") (pin "46") (pinfunction "BDBUS7_46") (pintype "bidirectional"))
    )
    (net (code "100") (name "unconnected-(U22-~{PWREN}-Pad60)") (class "Default")
      (node (ref "U22") (pin "60") (pinfunction "~{PWREN}_60") (pintype "output"))
    )
    (net (code "101") (name "unconnected-(U22-~{SUSPEND}-Pad36)") (class "Default")
      (node (ref "U22") (pin "36") (pinfunction "~{SUSPEND}_36") (pintype "output"))
    )
  )
)
